# CompPhysMP_V1_0_2.net
KiCad netlist of a schematic drawn in EAGLE
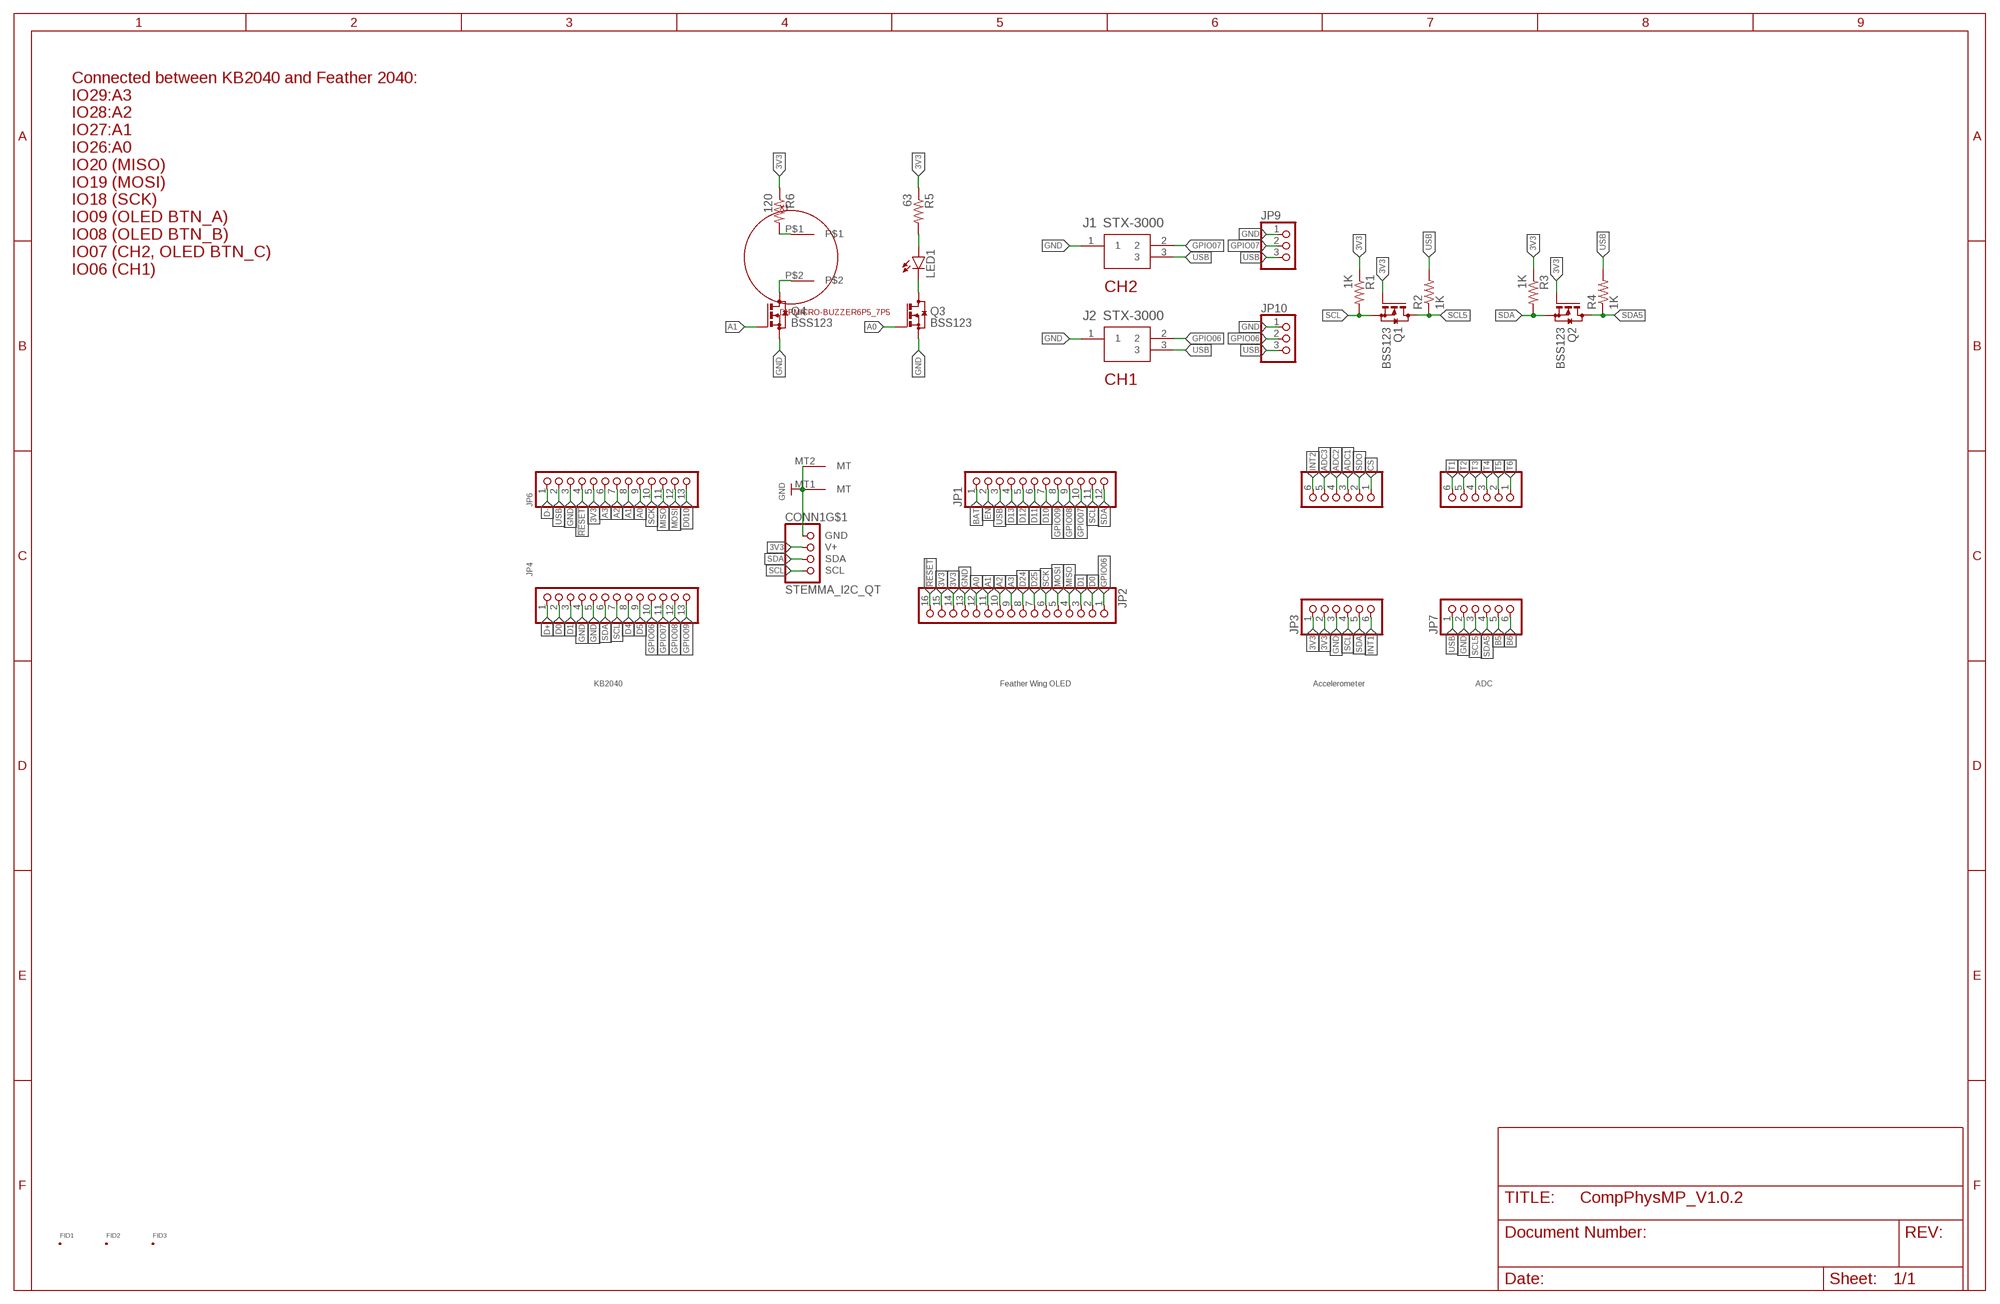
[diagram p0: schematic, sheet 1]

(export (version "E")
  (design (tool "Eeschema 10.0.6"))
  (components
    (comp (ref "CONN1")
      (value "STEMMA_I2C_QT")
      (footprint "eagle-import:JST_SH4")
      (libsource (lib "eagle-import") (part "STEMMA_I2C_QT"))
    )
    (comp (ref "FID1")
      (value "FID_50MIL")
      (footprint "eagle-import:FID_050")
      (libsource (lib "eagle-import") (part "FID_50MIL"))
    )
    (comp (ref "FID2")
      (value "FID_50MIL")
      (footprint "eagle-import:FID_050")
      (libsource (lib "eagle-import") (part "FID_50MIL"))
    )
    (comp (ref "FID3")
      (value "FID_50MIL")
      (footprint "eagle-import:FID_050")
      (libsource (lib "eagle-import") (part "FID_50MIL"))
    )
    (comp (ref "J1")
      (value "STX-3000")
      (footprint "eagle-import:STX3000")
      (fields (field (name "MOUSER_PART_NUMBER") "806-STX-3000"))
      (libsource (lib "eagle-import") (part "STX-3000"))
    )
    (comp (ref "J2")
      (value "STX-3000")
      (footprint "eagle-import:STX3000")
      (fields (field (name "MOUSER_PART_NUMBER") "806-STX-3000"))
      (libsource (lib "eagle-import") (part "STX-3000"))
    )
    (comp (ref "JP1")
      (value "PINHD-1X12")
      (footprint "eagle-import:1X12")
      (libsource (lib "eagle-import") (part "PINHD-1X12"))
    )
    (comp (ref "JP2")
      (value "PINHD-1X16")
      (footprint "eagle-import:1X16")
      (libsource (lib "eagle-import") (part "PINHD-1X16"))
    )
    (comp (ref "JP3")
      (value "HEADER-1X670MIL")
      (footprint "eagle-import:1X06_ROUND_70")
      (libsource (lib "eagle-import") (part "HEADER-1X670MIL"))
    )
    (comp (ref "JP4")
      (value "PINHD-1X13")
      (footprint "eagle-import:1X13")
      (libsource (lib "eagle-import") (part "PINHD-1X13"))
    )
    (comp (ref "JP5")
      (value "HEADER-1X670MIL")
      (footprint "eagle-import:1X06_ROUND_70")
      (libsource (lib "eagle-import") (part "HEADER-1X670MIL"))
    )
    (comp (ref "JP6")
      (value "PINHD-1X13")
      (footprint "eagle-import:1X13")
      (libsource (lib "eagle-import") (part "PINHD-1X13"))
    )
    (comp (ref "JP7")
      (value "HEADER-1X670MIL")
      (footprint "eagle-import:1X06_ROUND_70")
      (libsource (lib "eagle-import") (part "HEADER-1X670MIL"))
    )
    (comp (ref "JP8")
      (value "HEADER-1X670MIL")
      (footprint "eagle-import:1X06_ROUND_70")
      (libsource (lib "eagle-import") (part "HEADER-1X670MIL"))
    )
    (comp (ref "JP9")
      (value "PINHD-1X3SMALL-PADS")
      (footprint "eagle-import:1X03-BIG")
      (libsource (lib "eagle-import") (part "PINHD-1X3SMALL-PADS"))
    )
    (comp (ref "JP10")
      (value "PINHD-1X3SMALL-PADS")
      (footprint "eagle-import:1X03-BIG")
      (libsource (lib "eagle-import") (part "PINHD-1X3SMALL-PADS"))
    )
    (comp (ref "LED1")
      (value "LED5MM")
      (footprint "eagle-import:LED5MM")
      (libsource (lib "eagle-import") (part "LED5MM"))
    )
    (comp (ref "Q1")
      (value "BSS123")
      (footprint "eagle-import:SOT23")
      (libsource (lib "eagle-import") (part "BSS123"))
    )
    (comp (ref "Q2")
      (value "BSS123")
      (footprint "eagle-import:SOT23")
      (libsource (lib "eagle-import") (part "BSS123"))
    )
    (comp (ref "Q3")
      (value "BSS123")
      (footprint "eagle-import:SOT23")
      (libsource (lib "eagle-import") (part "BSS123"))
    )
    (comp (ref "Q4")
      (value "BSS123")
      (footprint "eagle-import:SOT23")
      (libsource (lib "eagle-import") (part "BSS123"))
    )
    (comp (ref "R1")
      (value "1K")
      (footprint "eagle-import:R0805")
      (libsource (lib "eagle-import") (part "R-US_R0805"))
    )
    (comp (ref "R2")
      (value "1K")
      (footprint "eagle-import:R0805")
      (libsource (lib "eagle-import") (part "R-US_R0805"))
    )
    (comp (ref "R3")
      (value "1K")
      (footprint "eagle-import:R0805")
      (libsource (lib "eagle-import") (part "R-US_R0805"))
    )
    (comp (ref "R4")
      (value "1K")
      (footprint "eagle-import:R0805")
      (libsource (lib "eagle-import") (part "R-US_R0805"))
    )
    (comp (ref "R5")
      (value "63")
      (footprint "eagle-import:R0805")
      (libsource (lib "eagle-import") (part "R-US_R0805"))
    )
    (comp (ref "R6")
      (value "120")
      (footprint "eagle-import:R0805")
      (libsource (lib "eagle-import") (part "R-US_R0805"))
    )
    (comp (ref "X1")
      (value "DIPMICRO-BUZZER6P5_7P5")
      (footprint "eagle-import:BUZZER-6P5-7P5")
      (libsource (lib "eagle-import") (part "DIPMICRO-BUZZER6P5_7P5"))
    )
  )
  (nets
    (net (code "1") (name "/~{RESET}") (class "Default")
      (node (ref "JP2") (pin "16") (pinfunction "16_16") (pintype "passive"))
      (node (ref "JP6") (pin "4") (pinfunction "4_4") (pintype "passive"))
    )
    (net (code "2") (name "3V3") (class "Default")
      (node (ref "CONN1") (pin "2") (pinfunction "V+_2") (pintype "passive"))
      (node (ref "JP2") (pin "14") (pinfunction "14_14") (pintype "passive"))
      (node (ref "JP2") (pin "15") (pinfunction "15_15") (pintype "passive"))
      (node (ref "JP3") (pin "1") (pinfunction "1_1") (pintype "passive"))
      (node (ref "JP3") (pin "2") (pinfunction "2_2") (pintype "passive"))
      (node (ref "JP6") (pin "5") (pinfunction "5_5") (pintype "passive"))
      (node (ref "Q1") (pin "1") (pinfunction "G_1") (pintype "passive"))
      (node (ref "Q2") (pin "1") (pinfunction "G_1") (pintype "passive"))
      (node (ref "R1") (pin "1") (pinfunction "1_1") (pintype "passive"))
      (node (ref "R3") (pin "1") (pinfunction "1_1") (pintype "passive"))
      (node (ref "R5") (pin "1") (pinfunction "1_1") (pintype "passive"))
      (node (ref "R6") (pin "1") (pinfunction "1_1") (pintype "passive"))
    )
    (net (code "3") (name "A0") (class "Default")
      (node (ref "JP2") (pin "12") (pinfunction "12_12") (pintype "passive"))
      (node (ref "JP6") (pin "9") (pinfunction "9_9") (pintype "passive"))
      (node (ref "Q3") (pin "1") (pinfunction "G_1") (pintype "passive"))
    )
    (net (code "4") (name "A1") (class "Default")
      (node (ref "JP2") (pin "11") (pinfunction "11_11") (pintype "passive"))
      (node (ref "JP6") (pin "8") (pinfunction "8_8") (pintype "passive"))
      (node (ref "Q4") (pin "1") (pinfunction "G_1") (pintype "passive"))
    )
    (net (code "5") (name "A2") (class "Default")
      (node (ref "JP2") (pin "10") (pinfunction "10_10") (pintype "passive"))
      (node (ref "JP6") (pin "7") (pinfunction "7_7") (pintype "passive"))
    )
    (net (code "6") (name "A3") (class "Default")
      (node (ref "JP2") (pin "9") (pinfunction "9_9") (pintype "passive"))
      (node (ref "JP6") (pin "6") (pinfunction "6_6") (pintype "passive"))
    )
    (net (code "7") (name "ADC1") (class "Default")
      (node (ref "JP5") (pin "3") (pinfunction "3_3") (pintype "passive"))
    )
    (net (code "8") (name "ADC2") (class "Default")
      (node (ref "JP5") (pin "4") (pinfunction "4_4") (pintype "passive"))
    )
    (net (code "9") (name "ADC3") (class "Default")
      (node (ref "JP5") (pin "5") (pinfunction "5_5") (pintype "passive"))
    )
    (net (code "10") (name "B5") (class "Default")
      (node (ref "JP7") (pin "5") (pinfunction "5_5") (pintype "passive"))
    )
    (net (code "11") (name "B6") (class "Default")
      (node (ref "JP7") (pin "6") (pinfunction "6_6") (pintype "passive"))
    )
    (net (code "12") (name "BAT") (class "Default")
      (node (ref "JP1") (pin "1") (pinfunction "1_1") (pintype "passive"))
    )
    (net (code "13") (name "CS") (class "Default")
      (node (ref "JP5") (pin "1") (pinfunction "1_1") (pintype "passive"))
    )
    (net (code "14") (name "D+") (class "Default")
      (node (ref "JP4") (pin "1") (pinfunction "1_1") (pintype "passive"))
    )
    (net (code "15") (name "D-") (class "Default")
      (node (ref "JP6") (pin "1") (pinfunction "1_1") (pintype "passive"))
    )
    (net (code "16") (name "D0") (class "Default")
      (node (ref "JP2") (pin "2") (pinfunction "2_2") (pintype "passive"))
      (node (ref "JP4") (pin "2") (pinfunction "2_2") (pintype "passive"))
    )
    (net (code "17") (name "D1") (class "Default")
      (node (ref "JP2") (pin "3") (pinfunction "3_3") (pintype "passive"))
      (node (ref "JP4") (pin "3") (pinfunction "3_3") (pintype "passive"))
    )
    (net (code "18") (name "D4") (class "Default")
      (node (ref "JP4") (pin "8") (pinfunction "8_8") (pintype "passive"))
    )
    (net (code "19") (name "D5") (class "Default")
      (node (ref "JP4") (pin "9") (pinfunction "9_9") (pintype "passive"))
    )
    (net (code "20") (name "D10") (class "Default")
      (node (ref "JP1") (pin "7") (pinfunction "7_7") (pintype "passive"))
    )
    (net (code "21") (name "D010") (class "Default")
      (node (ref "JP6") (pin "13") (pinfunction "13_13") (pintype "passive"))
    )
    (net (code "22") (name "D11") (class "Default")
      (node (ref "JP1") (pin "6") (pinfunction "6_6") (pintype "passive"))
    )
    (net (code "23") (name "D12") (class "Default")
      (node (ref "JP1") (pin "5") (pinfunction "5_5") (pintype "passive"))
    )
    (net (code "24") (name "D13") (class "Default")
      (node (ref "JP1") (pin "4") (pinfunction "4_4") (pintype "passive"))
    )
    (net (code "25") (name "D24") (class "Default")
      (node (ref "JP2") (pin "8") (pinfunction "8_8") (pintype "passive"))
    )
    (net (code "26") (name "D25") (class "Default")
      (node (ref "JP2") (pin "7") (pinfunction "7_7") (pintype "passive"))
    )
    (net (code "27") (name "EN") (class "Default")
      (node (ref "JP1") (pin "2") (pinfunction "2_2") (pintype "passive"))
    )
    (net (code "28") (name "GND") (class "Default")
      (node (ref "CONN1") (pin "1") (pinfunction "GND_1") (pintype "passive"))
      (node (ref "CONN1") (pin "MT1") (pinfunction "MT_MT1") (pintype "bidirectional"))
      (node (ref "CONN1") (pin "MT2") (pinfunction "MT_MT2") (pintype "bidirectional"))
      (node (ref "J1") (pin "1") (pinfunction "1_1") (pintype "bidirectional"))
      (node (ref "J2") (pin "1") (pinfunction "1_1") (pintype "bidirectional"))
      (node (ref "JP10") (pin "1") (pinfunction "1_1") (pintype "passive"))
      (node (ref "JP2") (pin "13") (pinfunction "13_13") (pintype "passive"))
      (node (ref "JP3") (pin "3") (pinfunction "3_3") (pintype "passive"))
      (node (ref "JP4") (pin "4") (pinfunction "4_4") (pintype "passive"))
      (node (ref "JP4") (pin "5") (pinfunction "5_5") (pintype "passive"))
      (node (ref "JP6") (pin "3") (pinfunction "3_3") (pintype "passive"))
      (node (ref "JP7") (pin "2") (pinfunction "2_2") (pintype "passive"))
      (node (ref "JP9") (pin "1") (pinfunction "1_1") (pintype "passive"))
      (node (ref "Q3") (pin "2") (pinfunction "S_2") (pintype "passive"))
      (node (ref "Q4") (pin "2") (pinfunction "S_2") (pintype "passive"))
    )
    (net (code "29") (name "GPIO06") (class "Default")
      (node (ref "J2") (pin "2") (pinfunction "2_2") (pintype "bidirectional"))
      (node (ref "JP10") (pin "2") (pinfunction "2_2") (pintype "passive"))
      (node (ref "JP2") (pin "1") (pinfunction "1_1") (pintype "passive"))
      (node (ref "JP4") (pin "10") (pinfunction "10_10") (pintype "passive"))
    )
    (net (code "30") (name "GPIO07") (class "Default")
      (node (ref "J1") (pin "2") (pinfunction "2_2") (pintype "bidirectional"))
      (node (ref "JP1") (pin "10") (pinfunction "10_10") (pintype "passive"))
      (node (ref "JP4") (pin "11") (pinfunction "11_11") (pintype "passive"))
      (node (ref "JP9") (pin "2") (pinfunction "2_2") (pintype "passive"))
    )
    (net (code "31") (name "GPIO08") (class "Default")
      (node (ref "JP1") (pin "9") (pinfunction "9_9") (pintype "passive"))
      (node (ref "JP4") (pin "12") (pinfunction "12_12") (pintype "passive"))
    )
    (net (code "32") (name "GPIO09") (class "Default")
      (node (ref "JP1") (pin "8") (pinfunction "8_8") (pintype "passive"))
      (node (ref "JP4") (pin "13") (pinfunction "13_13") (pintype "passive"))
    )
    (net (code "33") (name "INT1") (class "Default")
      (node (ref "JP3") (pin "6") (pinfunction "6_6") (pintype "passive"))
    )
    (net (code "34") (name "INT2") (class "Default")
      (node (ref "JP5") (pin "6") (pinfunction "6_6") (pintype "passive"))
    )
    (net (code "35") (name "MISO") (class "Default")
      (node (ref "JP2") (pin "4") (pinfunction "4_4") (pintype "passive"))
      (node (ref "JP6") (pin "11") (pinfunction "11_11") (pintype "passive"))
    )
    (net (code "36") (name "MOSI") (class "Default")
      (node (ref "JP2") (pin "5") (pinfunction "5_5") (pintype "passive"))
      (node (ref "JP6") (pin "12") (pinfunction "12_12") (pintype "passive"))
    )
    (net (code "37") (name "Net-(LED1-C)") (class "Default")
      (node (ref "LED1") (pin "K") (pinfunction "C_K") (pintype "passive"))
      (node (ref "Q3") (pin "3") (pinfunction "D_3") (pintype "passive"))
    )
    (net (code "38") (name "Net-(LED1-PadA)") (class "Default")
      (node (ref "LED1") (pin "A") (pinfunction "A_A") (pintype "passive"))
      (node (ref "R5") (pin "2") (pinfunction "2_2") (pintype "passive"))
    )
    (net (code "39") (name "Net-(Q4-D)") (class "Default")
      (node (ref "Q4") (pin "3") (pinfunction "D_3") (pintype "passive"))
      (node (ref "X1") (pin "P$2") (pinfunction "P$2_P$2") (pintype "bidirectional"))
    )
    (net (code "40") (name "Net-(R6-Pad2)") (class "Default")
      (node (ref "R6") (pin "2") (pinfunction "2_2") (pintype "passive"))
      (node (ref "X1") (pin "P$1") (pinfunction "P$1_P$1") (pintype "bidirectional"))
    )
    (net (code "41") (name "SCK") (class "Default")
      (node (ref "JP2") (pin "6") (pinfunction "6_6") (pintype "passive"))
      (node (ref "JP6") (pin "10") (pinfunction "10_10") (pintype "passive"))
    )
    (net (code "42") (name "SCL") (class "Default")
      (node (ref "CONN1") (pin "4") (pinfunction "SCL_4") (pintype "passive"))
      (node (ref "JP1") (pin "11") (pinfunction "11_11") (pintype "passive"))
      (node (ref "JP3") (pin "4") (pinfunction "4_4") (pintype "passive"))
      (node (ref "JP4") (pin "7") (pinfunction "7_7") (pintype "passive"))
      (node (ref "Q1") (pin "2") (pinfunction "S_2") (pintype "passive"))
      (node (ref "R1") (pin "2") (pinfunction "2_2") (pintype "passive"))
    )
    (net (code "43") (name "SCL5") (class "Default")
      (node (ref "JP7") (pin "3") (pinfunction "3_3") (pintype "passive"))
      (node (ref "Q1") (pin "3") (pinfunction "D_3") (pintype "passive"))
      (node (ref "R2") (pin "1") (pinfunction "1_1") (pintype "passive"))
    )
    (net (code "44") (name "SDA") (class "Default")
      (node (ref "CONN1") (pin "3") (pinfunction "SDA_3") (pintype "passive"))
      (node (ref "JP1") (pin "12") (pinfunction "12_12") (pintype "passive"))
      (node (ref "JP3") (pin "5") (pinfunction "5_5") (pintype "passive"))
      (node (ref "JP4") (pin "6") (pinfunction "6_6") (pintype "passive"))
      (node (ref "Q2") (pin "2") (pinfunction "S_2") (pintype "passive"))
      (node (ref "R3") (pin "2") (pinfunction "2_2") (pintype "passive"))
    )
    (net (code "45") (name "SDA5") (class "Default")
      (node (ref "JP7") (pin "4") (pinfunction "4_4") (pintype "passive"))
      (node (ref "Q2") (pin "3") (pinfunction "D_3") (pintype "passive"))
      (node (ref "R4") (pin "1") (pinfunction "1_1") (pintype "passive"))
    )
    (net (code "46") (name "SDO") (class "Default")
      (node (ref "JP5") (pin "2") (pinfunction "2_2") (pintype "passive"))
    )
    (net (code "47") (name "T1") (class "Default")
      (node (ref "JP8") (pin "6") (pinfunction "6_6") (pintype "passive"))
    )
    (net (code "48") (name "T2") (class "Default")
      (node (ref "JP8") (pin "5") (pinfunction "5_5") (pintype "passive"))
    )
    (net (code "49") (name "T3") (class "Default")
      (node (ref "JP8") (pin "4") (pinfunction "4_4") (pintype "passive"))
    )
    (net (code "50") (name "T4") (class "Default")
      (node (ref "JP8") (pin "3") (pinfunction "3_3") (pintype "passive"))
    )
    (net (code "51") (name "T5") (class "Default")
      (node (ref "JP8") (pin "2") (pinfunction "2_2") (pintype "passive"))
    )
    (net (code "52") (name "T6") (class "Default")
      (node (ref "JP8") (pin "1") (pinfunction "1_1") (pintype "passive"))
    )
    (net (code "53") (name "USB") (class "Default")
      (node (ref "J1") (pin "3") (pinfunction "3_3") (pintype "bidirectional"))
      (node (ref "J2") (pin "3") (pinfunction "3_3") (pintype "bidirectional"))
      (node (ref "JP1") (pin "3") (pinfunction "3_3") (pintype "passive"))
      (node (ref "JP10") (pin "3") (pinfunction "3_3") (pintype "passive"))
      (node (ref "JP6") (pin "2") (pinfunction "2_2") (pintype "passive"))
      (node (ref "JP7") (pin "1") (pinfunction "1_1") (pintype "passive"))
      (node (ref "JP9") (pin "3") (pinfunction "3_3") (pintype "passive"))
      (node (ref "R2") (pin "2") (pinfunction "2_2") (pintype "passive"))
      (node (ref "R4") (pin "2") (pinfunction "2_2") (pintype "passive"))
    )
  )
)
